# pdb_v4.net
KiCad netlist of a schematic drawn in EAGLE
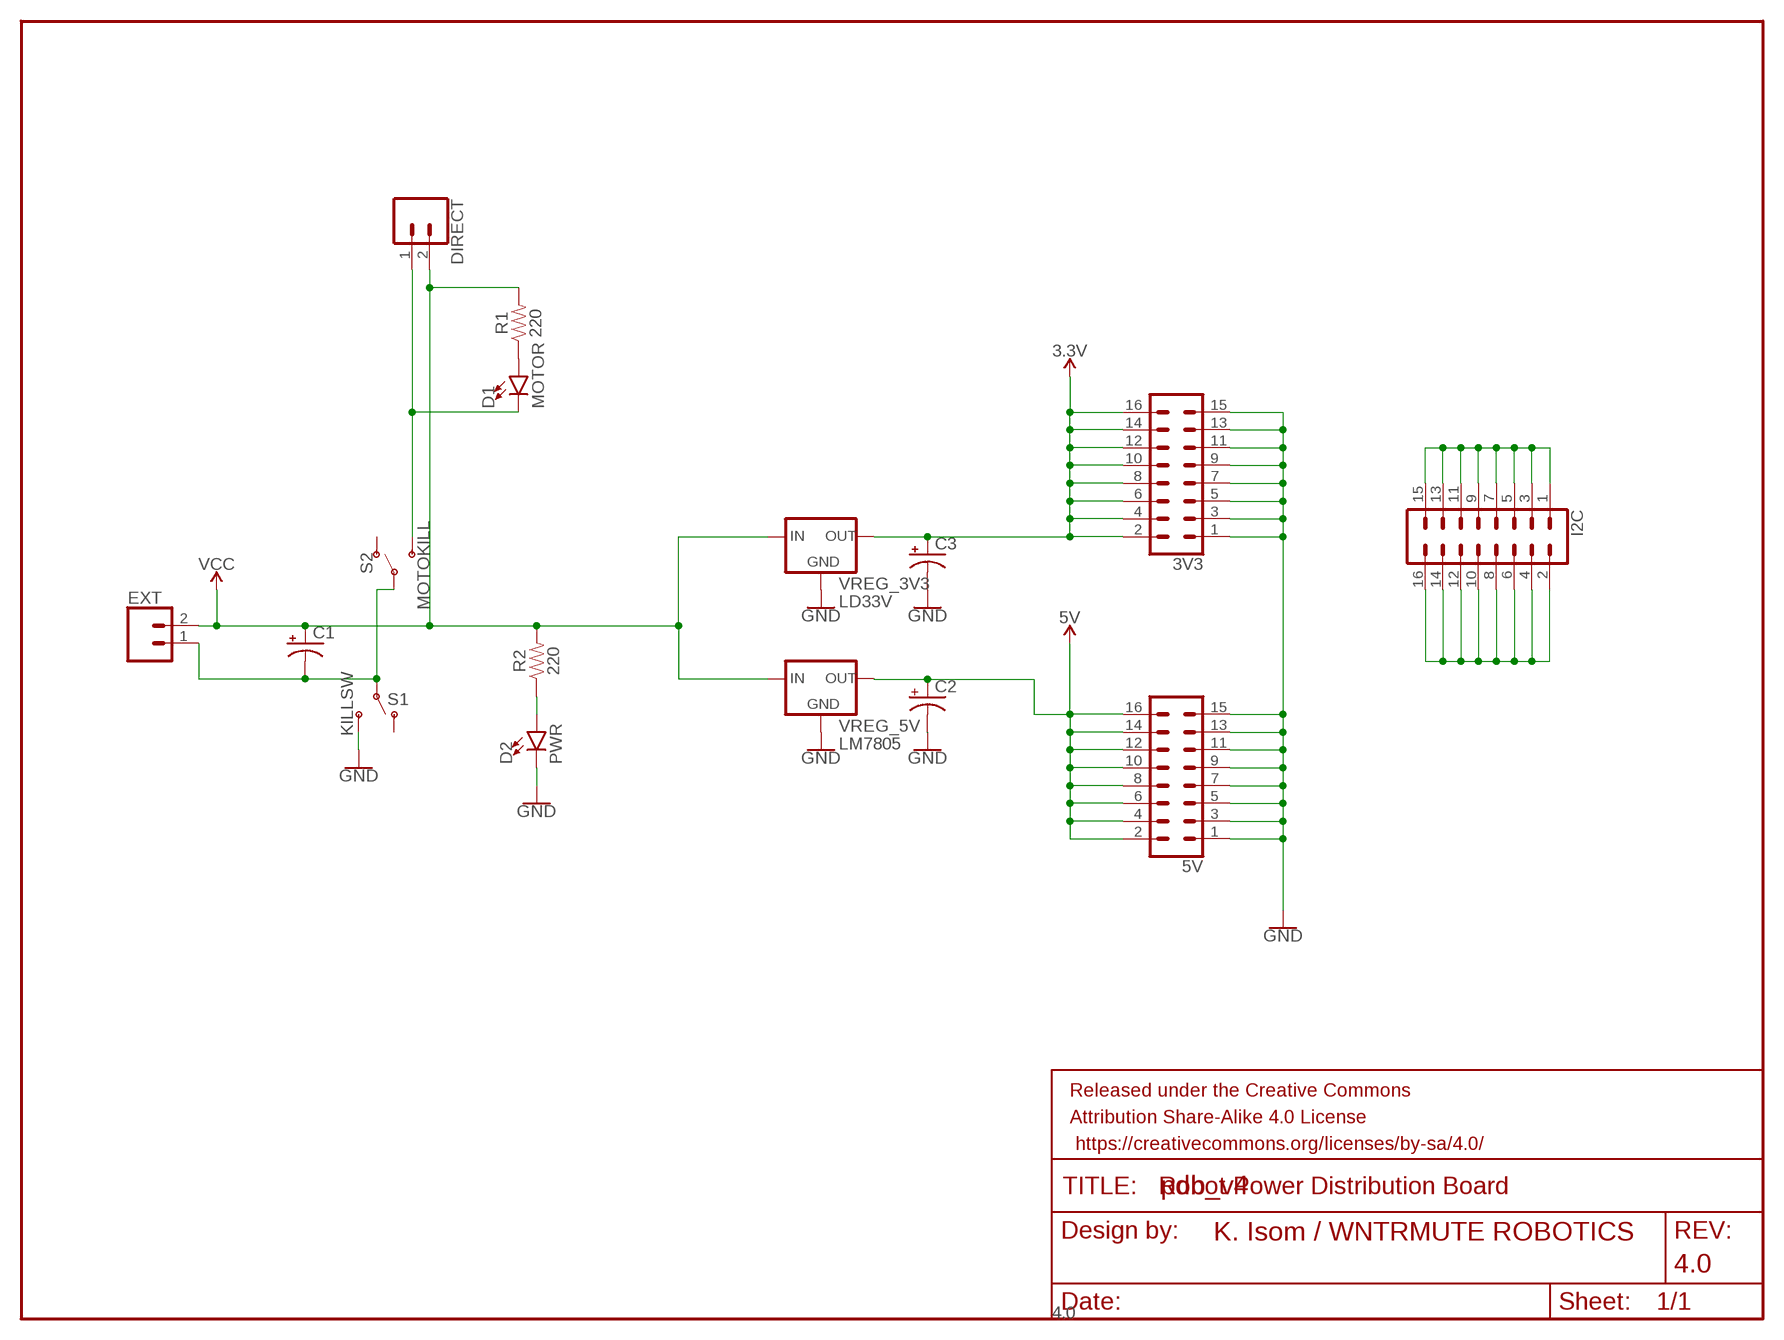
[diagram p0: schematic, sheet 1]

(export (version "E")
  (design (tool "Eeschema 10.0.6"))
  (components
    (comp (ref "3V3")
      (value "CONN_08X2_HEADER")
      (footprint "eagle-import:2X8")
      (libsource (lib "eagle-import") (part "CONN_08X2_HEADER"))
    )
    (comp (ref "5V")
      (value "CONN_08X2_HEADER")
      (footprint "eagle-import:2X8")
      (libsource (lib "eagle-import") (part "CONN_08X2_HEADER"))
    )
    (comp (ref "C1")
      (value "1000uF")
      (footprint "eagle-import:CPOL-RADIAL-5MM-10MM")
      (libsource (lib "eagle-import") (part "1000UF-RADIAL-5MM-25V-20%"))
    )
    (comp (ref "C2")
      (value "100uF")
      (footprint "eagle-import:E5-8,5")
      (libsource (lib "eagle-import") (part "CPOL-USE5-8.5"))
    )
    (comp (ref "C3")
      (value "100uF")
      (footprint "eagle-import:E5-8,5")
      (libsource (lib "eagle-import") (part "CPOL-USE5-8.5"))
    )
    (comp (ref "D1")
      (value "MOTOR")
      (footprint "eagle-import:LED_3MM")
      (libsource (lib "eagle-import") (part "LED3MM"))
    )
    (comp (ref "D2")
      (value "PWR")
      (footprint "eagle-import:LED_3MM")
      (libsource (lib "eagle-import") (part "LED3MM"))
    )
    (comp (ref "DIRECT")
      (value "CONN_025MM")
      (footprint "eagle-import:SCREWTERMINAL-5MM-2")
      (libsource (lib "eagle-import") (part "CONN_025MM"))
    )
    (comp (ref "EXT")
      (value "CONN_025MM")
      (footprint "eagle-import:SCREWTERMINAL-5MM-2")
      (libsource (lib "eagle-import") (part "CONN_025MM"))
    )
    (comp (ref "FRAME1")
      (value "FRAME-LETTERNO_PACKAGE")
      (footprint "eagle-import:DUMMY")
      (fields
        (field (name "DESIGNER") "K. Isom / WNTRMUTE ROBOTICS")
        (field (name "VERSION") "4.0")
        (field (name "DESIGNER_1") "K. Isom / WNTRMUTE ROBOTICS")
        (field (name "REV") "4.0")
        (field (name "VERSION_1") "4.0")
      )
      (libsource (lib "eagle-import") (part "FRAME-LETTERNO_PACKAGE"))
    )
    (comp (ref "I2C")
      (value "CONN_08X2_HEADER")
      (footprint "eagle-import:2X8")
      (libsource (lib "eagle-import") (part "CONN_08X2_HEADER"))
    )
    (comp (ref "R1")
      (value "220")
      (footprint "eagle-import:0603")
      (libsource (lib "eagle-import") (part "220OHM-0603-1/10W-1%"))
    )
    (comp (ref "R2")
      (value "220")
      (footprint "eagle-import:0603")
      (libsource (lib "eagle-import") (part "220OHM-0603-1/10W-1%"))
    )
    (comp (ref "S1")
      (value "KILLSW")
      (footprint "eagle-import:SWITCH_SPDT_PTH_11.6X4.0MM_LOCK")
      (libsource (lib "eagle-import") (part "SWITCH-SPDT-PTH-11.6X4.0MM-LOCK"))
    )
    (comp (ref "S2")
      (value "MOTOKILL")
      (footprint "eagle-import:SWITCH_SPDT_PTH_11.6X4.0MM_LOCK")
      (libsource (lib "eagle-import") (part "SWITCH-SPDT-PTH-11.6X4.0MM-LOCK"))
    )
    (comp (ref "VREG_3V3")
      (value "LD33V")
      (footprint "eagle-import:78XXL")
      (libsource (lib "eagle-import") (part "V_REG_LD1117VXX"))
    )
    (comp (ref "VREG_5V")
      (value "LM7805")
      (footprint "eagle-import:TO-220-ALT")
      (libsource (lib "eagle-import") (part "V_REG_78XX-TO-220"))
    )
  )
  (nets
    (net (code "1") (name "3.3V") (class "Default")
      (node (ref "3V3") (pin "10") (pinfunction "10_10") (pintype "passive"))
      (node (ref "3V3") (pin "12") (pinfunction "12_12") (pintype "passive"))
      (node (ref "3V3") (pin "14") (pinfunction "14_14") (pintype "passive"))
      (node (ref "3V3") (pin "16") (pinfunction "16_16") (pintype "passive"))
      (node (ref "3V3") (pin "2") (pinfunction "2_2") (pintype "passive"))
      (node (ref "3V3") (pin "4") (pinfunction "4_4") (pintype "passive"))
      (node (ref "3V3") (pin "6") (pinfunction "6_6") (pintype "passive"))
      (node (ref "3V3") (pin "8") (pinfunction "8_8") (pintype "passive"))
      (node (ref "C3") (pin "+") (pinfunction "+_+") (pintype "passive"))
      (node (ref "VREG_3V3") (pin "GND") (pinfunction "OUT_GND") (pintype "passive"))
    )
    (net (code "2") (name "5V") (class "Default")
      (node (ref "5V") (pin "10") (pinfunction "10_10") (pintype "passive"))
      (node (ref "5V") (pin "12") (pinfunction "12_12") (pintype "passive"))
      (node (ref "5V") (pin "14") (pinfunction "14_14") (pintype "passive"))
      (node (ref "5V") (pin "16") (pinfunction "16_16") (pintype "passive"))
      (node (ref "5V") (pin "2") (pinfunction "2_2") (pintype "passive"))
      (node (ref "5V") (pin "4") (pinfunction "4_4") (pintype "passive"))
      (node (ref "5V") (pin "6") (pinfunction "6_6") (pintype "passive"))
      (node (ref "5V") (pin "8") (pinfunction "8_8") (pintype "passive"))
      (node (ref "C2") (pin "+") (pinfunction "+_+") (pintype "passive"))
      (node (ref "VREG_5V") (pin "OUT") (pinfunction "OUT_OUT") (pintype "passive"))
    )
    (net (code "3") (name "GND") (class "Default")
      (node (ref "3V3") (pin "1") (pinfunction "1_1") (pintype "passive"))
      (node (ref "3V3") (pin "11") (pinfunction "11_11") (pintype "passive"))
      (node (ref "3V3") (pin "13") (pinfunction "13_13") (pintype "passive"))
      (node (ref "3V3") (pin "15") (pinfunction "15_15") (pintype "passive"))
      (node (ref "3V3") (pin "3") (pinfunction "3_3") (pintype "passive"))
      (node (ref "3V3") (pin "5") (pinfunction "5_5") (pintype "passive"))
      (node (ref "3V3") (pin "7") (pinfunction "7_7") (pintype "passive"))
      (node (ref "3V3") (pin "9") (pinfunction "9_9") (pintype "passive"))
      (node (ref "5V") (pin "1") (pinfunction "1_1") (pintype "passive"))
      (node (ref "5V") (pin "11") (pinfunction "11_11") (pintype "passive"))
      (node (ref "5V") (pin "13") (pinfunction "13_13") (pintype "passive"))
      (node (ref "5V") (pin "15") (pinfunction "15_15") (pintype "passive"))
      (node (ref "5V") (pin "3") (pinfunction "3_3") (pintype "passive"))
      (node (ref "5V") (pin "5") (pinfunction "5_5") (pintype "passive"))
      (node (ref "5V") (pin "7") (pinfunction "7_7") (pintype "passive"))
      (node (ref "5V") (pin "9") (pinfunction "9_9") (pintype "passive"))
      (node (ref "C2") (pin "-") (pinfunction "-_-") (pintype "passive"))
      (node (ref "C3") (pin "-") (pinfunction "-_-") (pintype "passive"))
      (node (ref "D2") (pin "K") (pinfunction "C_K") (pintype "passive"))
      (node (ref "S1") (pin "3") (pinfunction "S_3") (pintype "passive"))
      (node (ref "VREG_3V3") (pin "IN") (pinfunction "GND_IN") (pintype "input"))
      (node (ref "VREG_5V") (pin "GND") (pinfunction "GND_GND") (pintype "input"))
    )
    (net (code "4") (name "Net-(D1-C)") (class "Default")
      (node (ref "D1") (pin "K") (pinfunction "C_K") (pintype "passive"))
      (node (ref "DIRECT") (pin "1") (pinfunction "1_1") (pintype "passive"))
      (node (ref "S2") (pin "3") (pinfunction "S_3") (pintype "passive"))
    )
    (net (code "5") (name "Net-(D1-PadA)") (class "Default")
      (node (ref "D1") (pin "A") (pinfunction "A_A") (pintype "passive"))
      (node (ref "R1") (pin "1") (pinfunction "1_1") (pintype "passive"))
    )
    (net (code "6") (name "Net-(D2-PadA)") (class "Default")
      (node (ref "D2") (pin "A") (pinfunction "A_A") (pintype "passive"))
      (node (ref "R2") (pin "1") (pinfunction "1_1") (pintype "passive"))
    )
    (net (code "7") (name "Net-(I2C-Pad1)") (class "Default")
      (node (ref "I2C") (pin "1") (pinfunction "1_1") (pintype "passive"))
      (node (ref "I2C") (pin "11") (pinfunction "11_11") (pintype "passive"))
      (node (ref "I2C") (pin "13") (pinfunction "13_13") (pintype "passive"))
      (node (ref "I2C") (pin "15") (pinfunction "15_15") (pintype "passive"))
      (node (ref "I2C") (pin "3") (pinfunction "3_3") (pintype "passive"))
      (node (ref "I2C") (pin "5") (pinfunction "5_5") (pintype "passive"))
      (node (ref "I2C") (pin "7") (pinfunction "7_7") (pintype "passive"))
      (node (ref "I2C") (pin "9") (pinfunction "9_9") (pintype "passive"))
    )
    (net (code "8") (name "Net-(I2C-Pad10)") (class "Default")
      (node (ref "I2C") (pin "10") (pinfunction "10_10") (pintype "passive"))
      (node (ref "I2C") (pin "12") (pinfunction "12_12") (pintype "passive"))
      (node (ref "I2C") (pin "14") (pinfunction "14_14") (pintype "passive"))
      (node (ref "I2C") (pin "16") (pinfunction "16_16") (pintype "passive"))
      (node (ref "I2C") (pin "2") (pinfunction "2_2") (pintype "passive"))
      (node (ref "I2C") (pin "4") (pinfunction "4_4") (pintype "passive"))
      (node (ref "I2C") (pin "6") (pinfunction "6_6") (pintype "passive"))
      (node (ref "I2C") (pin "8") (pinfunction "8_8") (pintype "passive"))
    )
    (net (code "9") (name "Net-(S1-P)") (class "Default")
      (node (ref "C1") (pin "-") (pinfunction "-_-") (pintype "passive"))
      (node (ref "EXT") (pin "1") (pinfunction "1_1") (pintype "passive"))
      (node (ref "S1") (pin "2") (pinfunction "P_2") (pintype "passive"))
      (node (ref "S2") (pin "2") (pinfunction "P_2") (pintype "passive"))
    )
    (net (code "10") (name "VCC") (class "Default")
      (node (ref "C1") (pin "+") (pinfunction "+_+") (pintype "passive"))
      (node (ref "DIRECT") (pin "2") (pinfunction "2_2") (pintype "passive"))
      (node (ref "EXT") (pin "2") (pinfunction "2_2") (pintype "passive"))
      (node (ref "R1") (pin "2") (pinfunction "2_2") (pintype "passive"))
      (node (ref "R2") (pin "2") (pinfunction "2_2") (pintype "passive"))
      (node (ref "VREG_3V3") (pin "OUT") (pinfunction "IN_OUT") (pintype "input"))
      (node (ref "VREG_5V") (pin "IN") (pinfunction "IN_IN") (pintype "input"))
    )
    (net (code "11") (name "unconnected-(S1-O-Pad1)") (class "Default")
      (node (ref "S1") (pin "1") (pinfunction "O_1") (pintype "passive"))
    )
    (net (code "12") (name "unconnected-(S2-O-Pad1)") (class "Default")
      (node (ref "S2") (pin "1") (pinfunction "O_1") (pintype "passive"))
    )
  )
)
